# ESP8266_ESP-01_Schematic.net
KiCad netlist of a schematic drawn in Altium Designer
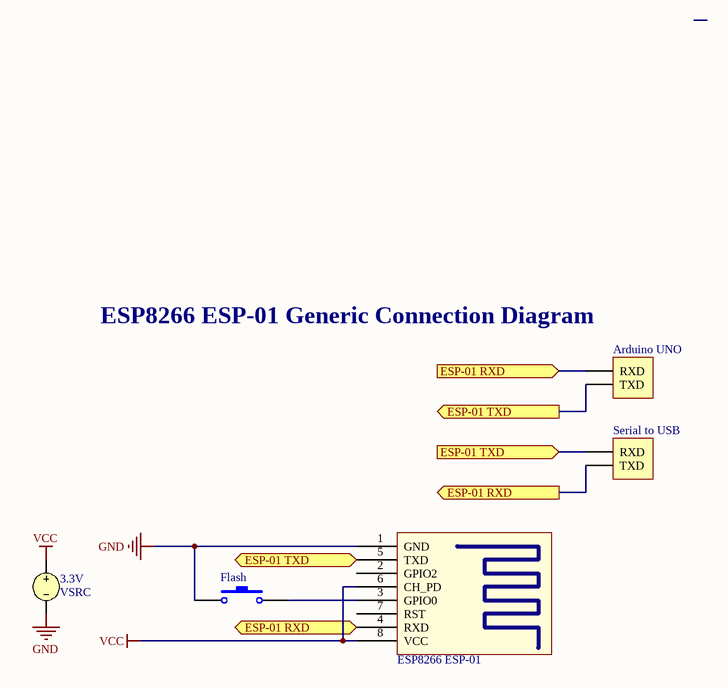
[diagram p0: ESP8266 ESP-01 Schematic.SchDoc]

(export (version "E")
  (design (tool "Eeschema 10.0.6"))
  (components
    (comp (ref "3.3V")
      (value "VSRC")
      (description "Voltage Source")
      (fields (field (name "PUBLISHER") "Altium Limited"))
      (libsource (lib "Simulation Sources") (part "VSRC"))
    )
    (comp (ref "Arduino UNO")
      (value "Header 2")
      (footprint "HDR1X2")
      (description "Header, 2-Pin")
      (fields (field (name "PUBLISHER") "Altium Limited"))
      (libsource (lib "Miscellaneous Connectors") (part "Header 2"))
    )
    (comp (ref "ESP-01")
      (value "ESP8266 ESP-01")
      (footprint "ESP8266:ESP8266 ESP-07")
      (libsource (lib "ESP8266") (part "ESP8266 ESP-01"))
    )
    (comp (ref "Flash")
      (value "SW-PB")
      (footprint "SPST-2")
      (description "Switch")
      (fields (field (name "PUBLISHER") "Altium Limited"))
      (libsource (lib "Miscellaneous Devices") (part "SW-PB"))
    )
    (comp (ref "Serial to USB")
      (value "Header 2")
      (footprint "HDR1X2")
      (description "Header, 2-Pin")
      (fields (field (name "PUBLISHER") "Altium Limited"))
      (libsource (lib "Miscellaneous Connectors") (part "Header 2"))
    )
  )
  (nets
    (net (code "1") (name "/ESP-01 RXD") (class "Default")
      (node (ref "Arduino UNO") (pin "1") (pinfunction "RXD_1") (pintype "passive"))
      (node (ref "ESP-01") (pin "4") (pinfunction "RXD_4") (pintype "passive"))
      (node (ref "Serial to USB") (pin "2") (pinfunction "TXD_2") (pintype "passive"))
    )
    (net (code "2") (name "/ESP-01 TXD") (class "Default")
      (node (ref "Arduino UNO") (pin "2") (pinfunction "TXD_2") (pintype "passive"))
      (node (ref "ESP-01") (pin "5") (pinfunction "TXD_5") (pintype "passive"))
      (node (ref "Serial to USB") (pin "1") (pinfunction "RXD_1") (pintype "passive"))
    )
    (net (code "3") (name "GND") (class "Default")
      (node (ref "3.3V") (pin "2") (pinfunction "2_2") (pintype "passive"))
      (node (ref "ESP-01") (pin "1") (pinfunction "GND_1") (pintype "passive"))
      (node (ref "Flash") (pin "1") (pinfunction "1_1") (pintype "passive"))
    )
    (net (code "4") (name "Net-(ESP-01-GPIO0)") (class "Default")
      (node (ref "ESP-01") (pin "3") (pinfunction "GPIO0_3") (pintype "passive"))
      (node (ref "Flash") (pin "2") (pinfunction "2_2") (pintype "passive"))
    )
    (net (code "5") (name "VCC") (class "Default")
      (node (ref "3.3V") (pin "1") (pinfunction "1_1") (pintype "passive"))
      (node (ref "ESP-01") (pin "6") (pinfunction "CH_PD_6") (pintype "passive"))
      (node (ref "ESP-01") (pin "8") (pinfunction "VCC_8") (pintype "passive"))
    )
    (net (code "6") (name "unconnected-(ESP-01-GPIO2-Pad2)") (class "Default")
      (node (ref "ESP-01") (pin "2") (pinfunction "GPIO2_2") (pintype "passive"))
    )
    (net (code "7") (name "unconnected-(ESP-01-RST-Pad7)") (class "Default")
      (node (ref "ESP-01") (pin "7") (pinfunction "RST_7") (pintype "passive"))
    )
  )
)
